# main.net
KiCad netlist of a schematic drawn in Altium Designer
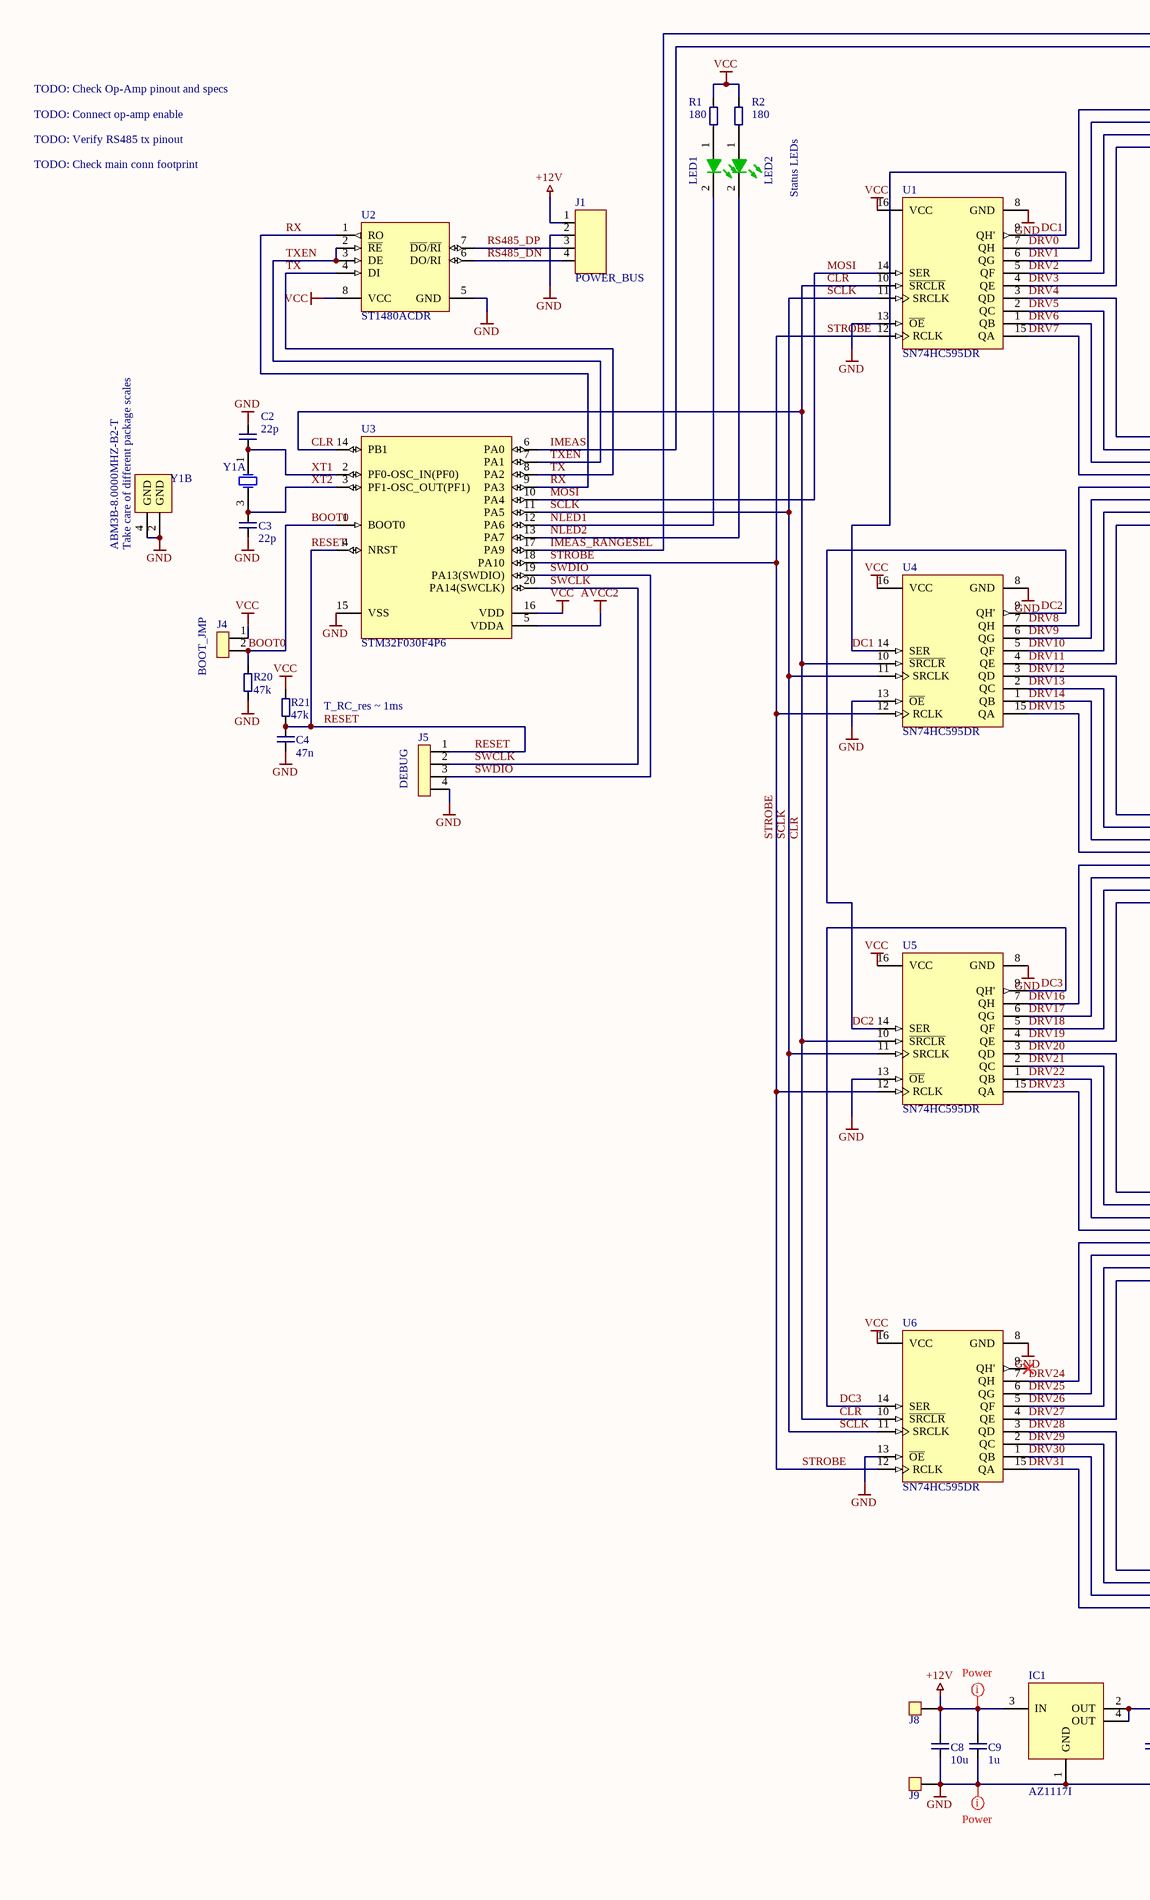
[diagram p0: main.SchDoc, left]
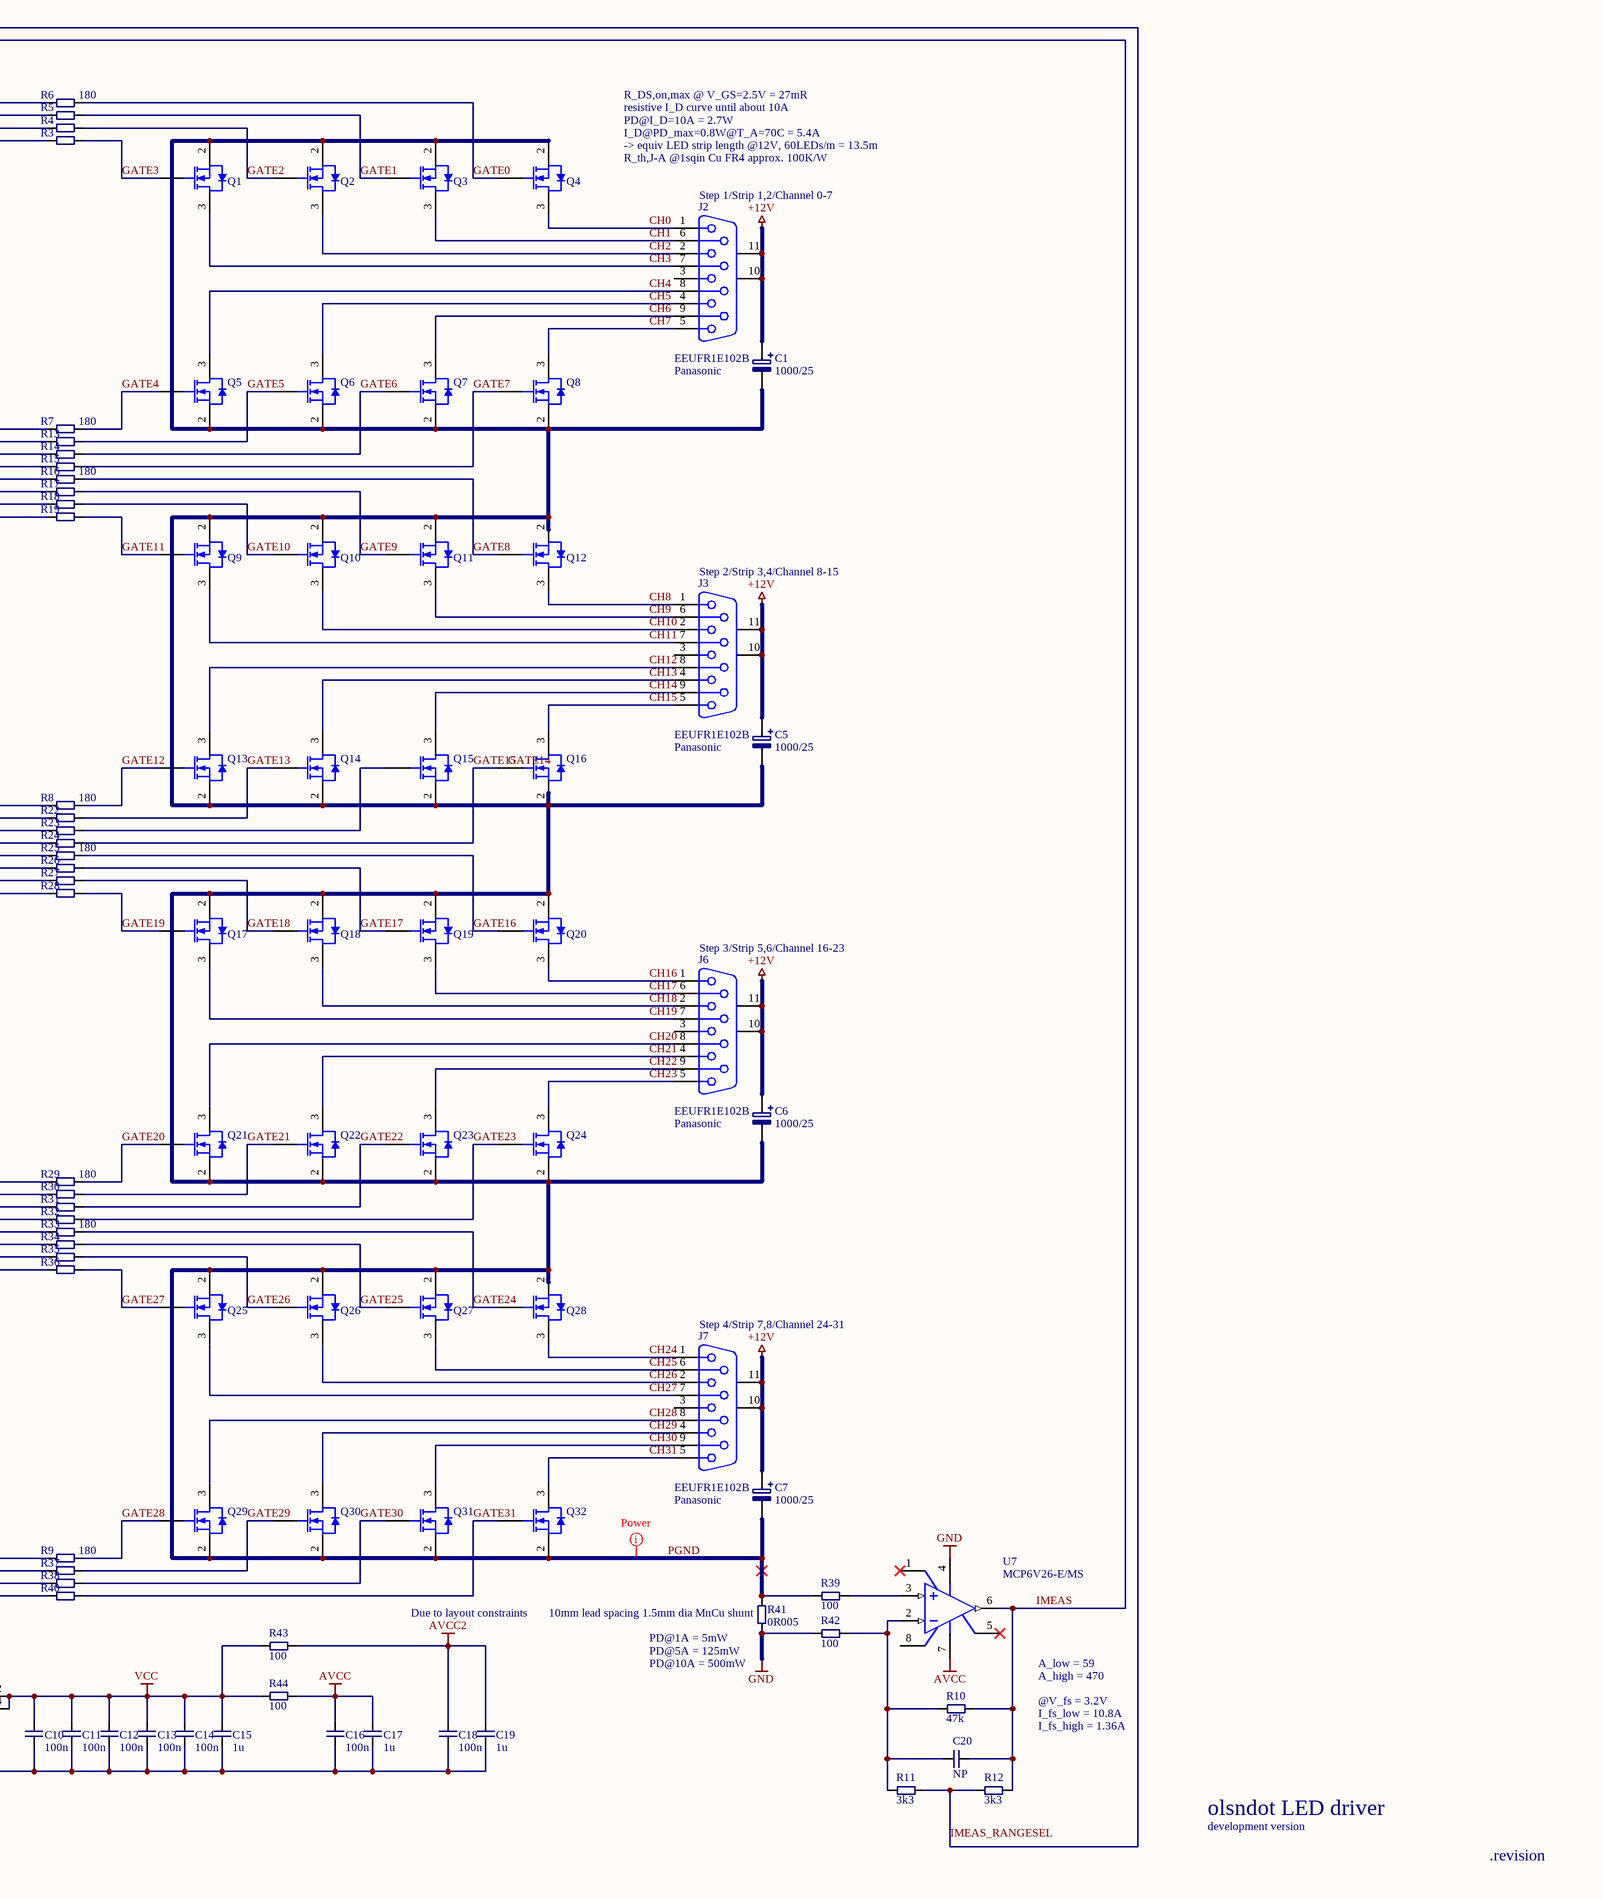
[diagram p1: main.SchDoc, right]

(export (version "E")
  (design (tool "Eeschema 10.0.6"))
  (components
    (comp (ref "C1")
      (value "1000/25")
      (footprint "ELKO_10mm_RM5")
      (fields (field (name "MFG PART NO") "EEUFR1E102B") (field (name "MFG") "Panasonic"))
      (libsource (lib "components") (part "ELKO"))
    )
    (comp (ref "C2")
      (value "22p")
      (footprint "J1-0603")
      (description "Capacitor")
      (libsource (lib "components") (part "C"))
    )
    (comp (ref "C3")
      (value "22p")
      (footprint "J1-0603")
      (description "Capacitor")
      (libsource (lib "components") (part "C"))
    )
    (comp (ref "C4")
      (value "47n")
      (footprint "J1-0603")
      (description "Capacitor")
      (libsource (lib "components") (part "C"))
    )
    (comp (ref "C5")
      (value "1000/25")
      (footprint "ELKO_10mm_RM5")
      (fields (field (name "MFG PART NO") "EEUFR1E102B") (field (name "MFG") "Panasonic"))
      (libsource (lib "components") (part "ELKO"))
    )
    (comp (ref "C6")
      (value "1000/25")
      (footprint "ELKO_10mm_RM5")
      (fields (field (name "MFG PART NO") "EEUFR1E102B") (field (name "MFG") "Panasonic"))
      (libsource (lib "components") (part "ELKO"))
    )
    (comp (ref "C7")
      (value "1000/25")
      (footprint "ELKO_10mm_RM5")
      (fields (field (name "MFG PART NO") "EEUFR1E102B") (field (name "MFG") "Panasonic"))
      (libsource (lib "components") (part "ELKO"))
    )
    (comp (ref "C8")
      (value "10u")
      (footprint "6-0805_M")
      (description "Capacitor")
      (libsource (lib "components") (part "C"))
    )
    (comp (ref "C9")
      (value "1u")
      (footprint "6-0805_M")
      (description "Capacitor")
      (libsource (lib "components") (part "C"))
    )
    (comp (ref "C10")
      (value "100n")
      (footprint "J1-0603")
      (description "Capacitor")
      (libsource (lib "components") (part "C"))
    )
    (comp (ref "C11")
      (value "100n")
      (footprint "J1-0603")
      (description "Capacitor")
      (libsource (lib "components") (part "C"))
    )
    (comp (ref "C12")
      (value "100n")
      (footprint "J1-0603")
      (description "Capacitor")
      (libsource (lib "components") (part "C"))
    )
    (comp (ref "C13")
      (value "100n")
      (footprint "J1-0603")
      (description "Capacitor")
      (libsource (lib "components") (part "C"))
    )
    (comp (ref "C14")
      (value "100n")
      (footprint "J1-0603")
      (description "Capacitor")
      (libsource (lib "components") (part "C"))
    )
    (comp (ref "C15")
      (value "1u")
      (footprint "6-0805_M")
      (description "Capacitor")
      (libsource (lib "components") (part "C"))
    )
    (comp (ref "C16")
      (value "100n")
      (footprint "J1-0603")
      (description "Capacitor")
      (libsource (lib "components") (part "C"))
    )
    (comp (ref "C17")
      (value "1u")
      (footprint "6-0805_M")
      (description "Capacitor")
      (libsource (lib "components") (part "C"))
    )
    (comp (ref "C18")
      (value "100n")
      (footprint "J1-0603")
      (description "Capacitor")
      (libsource (lib "components") (part "C"))
    )
    (comp (ref "C19")
      (value "1u")
      (footprint "J1-0603")
      (description "Capacitor")
      (libsource (lib "components") (part "C"))
    )
    (comp (ref "C20")
      (value "NP")
      (footprint "J1-0603")
      (description "Capacitor")
      (libsource (lib "components") (part "C"))
    )
    (comp (ref "IC1")
      (value "AZ1117I")
      (footprint "SOT223_M")
      (description "LDO, industrial temp range")
      (libsource (lib "components") (part "AZ1117I"))
    )
    (comp (ref "J1")
      (value "POWER_BUS")
      (footprint "TB_5.08_4P_FLANGE")
      (libsource (lib "components") (part "Phoenix_PT1,5/4-5,0H"))
    )
    (comp (ref "J2")
      (value "Step 1/Strip 1,2/Channel 0-7")
      (footprint "DSUB1.385-2H9")
      (description "Receptacle Assembly, 9 Position, Right Angle")
      (fields (field (name "PUBLISHER") "Altium Limited"))
      (libsource (lib "Miscellaneous Connectors") (part "D Connector 9"))
    )
    (comp (ref "J3")
      (value "Step 2/Strip 3,4/Channel 8-15")
      (footprint "DSUB1.385-2H9")
      (description "Receptacle Assembly, 9 Position, Right Angle")
      (fields (field (name "PUBLISHER") "Altium Limited"))
      (libsource (lib "Miscellaneous Connectors") (part "D Connector 9"))
    )
    (comp (ref "J4")
      (value "BOOT_JMP")
      (footprint "JUMPER_2P")
      (description "Jumper")
      (libsource (lib "components") (part "JUMPER"))
    )
    (comp (ref "J5")
      (value "DEBUG")
      (footprint "PINHD_4x1_100mil")
      (description "Pin Header 4x1 pin")
      (libsource (lib "components") (part "PH_4x1"))
    )
    (comp (ref "J6")
      (value "Step 3/Strip 5,6/Channel 16-23")
      (footprint "DSUB1.385-2H9")
      (description "Receptacle Assembly, 9 Position, Right Angle")
      (fields (field (name "PUBLISHER") "Altium Limited"))
      (libsource (lib "Miscellaneous Connectors") (part "D Connector 9"))
    )
    (comp (ref "J7")
      (value "Step 4/Strip 7,8/Channel 24-31")
      (footprint "DSUB1.385-2H9")
      (description "Receptacle Assembly, 9 Position, Right Angle")
      (fields (field (name "PUBLISHER") "Altium Limited"))
      (libsource (lib "Miscellaneous Connectors") (part "D Connector 9"))
    )
    (comp (ref "J8") (value "+12V") (libsource (lib "components") (part "TESTPOINT")))
    (comp (ref "J9") (value "GND") (libsource (lib "components") (part "TESTPOINT")))
    (comp (ref "LED1")
      (value "KP-1608MGC")
      (footprint "KING-0603LED_GREEN_V")
      (description "LED, SMT, 0603(1608), 1.1mm thickness, Green")
      (fields (field (name "MANUFACTURER") "Kingbright"))
      (libsource (lib "components") (part "CMP-0404-00001-1"))
    )
    (comp (ref "LED2")
      (value "KP-1608MGC")
      (footprint "KING-0603LED_GREEN_V")
      (description "LED, SMT, 0603(1608), 1.1mm thickness, Green")
      (fields (field (name "MANUFACTURER") "Kingbright"))
      (libsource (lib "components") (part "CMP-0404-00001-1"))
    )
    (comp (ref "Q1")
      (value "IRLML6244TRPbF")
      (footprint "ONSC-SOT-23-3-318-08_V")
      (description "Power MOSFET, 500 mA, 60 V, N-Channel, 3-Pin SOT-23, Pb-Free, Tape and Reel")
      (fields (field (name "MANUFACTURER") "On Semiconductor") (field (name "PARTNUMBER") "NVBF170LT1G"))
      (libsource (lib "Altium Content Vault") (part "ONSC-NMOS-G1S2D3-3"))
    )
    (comp (ref "Q2")
      (value "IRLML6244TRPbF")
      (footprint "ONSC-SOT-23-3-318-08_V")
      (description "Power MOSFET, 500 mA, 60 V, N-Channel, 3-Pin SOT-23, Pb-Free, Tape and Reel")
      (fields (field (name "MANUFACTURER") "On Semiconductor") (field (name "PARTNUMBER") "NVBF170LT1G"))
      (libsource (lib "Altium Content Vault") (part "ONSC-NMOS-G1S2D3-3"))
    )
    (comp (ref "Q3")
      (value "IRLML6244TRPbF")
      (footprint "ONSC-SOT-23-3-318-08_V")
      (description "Power MOSFET, 500 mA, 60 V, N-Channel, 3-Pin SOT-23, Pb-Free, Tape and Reel")
      (fields (field (name "MANUFACTURER") "On Semiconductor") (field (name "PARTNUMBER") "NVBF170LT1G"))
      (libsource (lib "Altium Content Vault") (part "ONSC-NMOS-G1S2D3-3"))
    )
    (comp (ref "Q4")
      (value "IRLML6244TRPbF")
      (footprint "ONSC-SOT-23-3-318-08_V")
      (description "Power MOSFET, 500 mA, 60 V, N-Channel, 3-Pin SOT-23, Pb-Free, Tape and Reel")
      (fields (field (name "MANUFACTURER") "On Semiconductor") (field (name "PARTNUMBER") "NVBF170LT1G"))
      (libsource (lib "Altium Content Vault") (part "ONSC-NMOS-G1S2D3-3"))
    )
    (comp (ref "Q5")
      (value "IRLML6244TRPbF")
      (footprint "ONSC-SOT-23-3-318-08_V")
      (description "Power MOSFET, 500 mA, 60 V, N-Channel, 3-Pin SOT-23, Pb-Free, Tape and Reel")
      (fields (field (name "MANUFACTURER") "On Semiconductor") (field (name "PARTNUMBER") "NVBF170LT1G"))
      (libsource (lib "Altium Content Vault") (part "ONSC-NMOS-G1S2D3-3"))
    )
    (comp (ref "Q6")
      (value "IRLML6244TRPbF")
      (footprint "ONSC-SOT-23-3-318-08_V")
      (description "Power MOSFET, 500 mA, 60 V, N-Channel, 3-Pin SOT-23, Pb-Free, Tape and Reel")
      (fields (field (name "MANUFACTURER") "On Semiconductor") (field (name "PARTNUMBER") "NVBF170LT1G"))
      (libsource (lib "Altium Content Vault") (part "ONSC-NMOS-G1S2D3-3"))
    )
    (comp (ref "Q7")
      (value "IRLML6244TRPbF")
      (footprint "ONSC-SOT-23-3-318-08_V")
      (description "Power MOSFET, 500 mA, 60 V, N-Channel, 3-Pin SOT-23, Pb-Free, Tape and Reel")
      (fields (field (name "MANUFACTURER") "On Semiconductor") (field (name "PARTNUMBER") "NVBF170LT1G"))
      (libsource (lib "Altium Content Vault") (part "ONSC-NMOS-G1S2D3-3"))
    )
    (comp (ref "Q8")
      (value "IRLML6244TRPbF")
      (footprint "ONSC-SOT-23-3-318-08_V")
      (description "Power MOSFET, 500 mA, 60 V, N-Channel, 3-Pin SOT-23, Pb-Free, Tape and Reel")
      (fields (field (name "MANUFACTURER") "On Semiconductor") (field (name "PARTNUMBER") "NVBF170LT1G"))
      (libsource (lib "Altium Content Vault") (part "ONSC-NMOS-G1S2D3-3"))
    )
    (comp (ref "Q9")
      (value "IRLML6244TRPbF")
      (footprint "ONSC-SOT-23-3-318-08_V")
      (description "Power MOSFET, 500 mA, 60 V, N-Channel, 3-Pin SOT-23, Pb-Free, Tape and Reel")
      (fields (field (name "MANUFACTURER") "On Semiconductor") (field (name "PARTNUMBER") "NVBF170LT1G"))
      (libsource (lib "Altium Content Vault") (part "ONSC-NMOS-G1S2D3-3"))
    )
    (comp (ref "Q10")
      (value "IRLML6244TRPbF")
      (footprint "ONSC-SOT-23-3-318-08_V")
      (description "Power MOSFET, 500 mA, 60 V, N-Channel, 3-Pin SOT-23, Pb-Free, Tape and Reel")
      (fields (field (name "MANUFACTURER") "On Semiconductor") (field (name "PARTNUMBER") "NVBF170LT1G"))
      (libsource (lib "Altium Content Vault") (part "ONSC-NMOS-G1S2D3-3"))
    )
    (comp (ref "Q11")
      (value "IRLML6244TRPbF")
      (footprint "ONSC-SOT-23-3-318-08_V")
      (description "Power MOSFET, 500 mA, 60 V, N-Channel, 3-Pin SOT-23, Pb-Free, Tape and Reel")
      (fields (field (name "MANUFACTURER") "On Semiconductor") (field (name "PARTNUMBER") "NVBF170LT1G"))
      (libsource (lib "Altium Content Vault") (part "ONSC-NMOS-G1S2D3-3"))
    )
    (comp (ref "Q12")
      (value "IRLML6244TRPbF")
      (footprint "ONSC-SOT-23-3-318-08_V")
      (description "Power MOSFET, 500 mA, 60 V, N-Channel, 3-Pin SOT-23, Pb-Free, Tape and Reel")
      (fields (field (name "MANUFACTURER") "On Semiconductor") (field (name "PARTNUMBER") "NVBF170LT1G"))
      (libsource (lib "Altium Content Vault") (part "ONSC-NMOS-G1S2D3-3"))
    )
    (comp (ref "Q13")
      (value "IRLML6244TRPbF")
      (footprint "ONSC-SOT-23-3-318-08_V")
      (description "Power MOSFET, 500 mA, 60 V, N-Channel, 3-Pin SOT-23, Pb-Free, Tape and Reel")
      (fields (field (name "MANUFACTURER") "On Semiconductor") (field (name "PARTNUMBER") "NVBF170LT1G"))
      (libsource (lib "Altium Content Vault") (part "ONSC-NMOS-G1S2D3-3"))
    )
    (comp (ref "Q14")
      (value "IRLML6244TRPbF")
      (footprint "ONSC-SOT-23-3-318-08_V")
      (description "Power MOSFET, 500 mA, 60 V, N-Channel, 3-Pin SOT-23, Pb-Free, Tape and Reel")
      (fields (field (name "MANUFACTURER") "On Semiconductor") (field (name "PARTNUMBER") "NVBF170LT1G"))
      (libsource (lib "Altium Content Vault") (part "ONSC-NMOS-G1S2D3-3"))
    )
    (comp (ref "Q15")
      (value "IRLML6244TRPbF")
      (footprint "ONSC-SOT-23-3-318-08_V")
      (description "Power MOSFET, 500 mA, 60 V, N-Channel, 3-Pin SOT-23, Pb-Free, Tape and Reel")
      (fields (field (name "MANUFACTURER") "On Semiconductor") (field (name "PARTNUMBER") "NVBF170LT1G"))
      (libsource (lib "Altium Content Vault") (part "ONSC-NMOS-G1S2D3-3"))
    )
    (comp (ref "Q16")
      (value "IRLML6244TRPbF")
      (footprint "ONSC-SOT-23-3-318-08_V")
      (description "Power MOSFET, 500 mA, 60 V, N-Channel, 3-Pin SOT-23, Pb-Free, Tape and Reel")
      (fields (field (name "MANUFACTURER") "On Semiconductor") (field (name "PARTNUMBER") "NVBF170LT1G"))
      (libsource (lib "Altium Content Vault") (part "ONSC-NMOS-G1S2D3-3"))
    )
    (comp (ref "Q17")
      (value "IRLML6244TRPbF")
      (footprint "ONSC-SOT-23-3-318-08_V")
      (description "Power MOSFET, 500 mA, 60 V, N-Channel, 3-Pin SOT-23, Pb-Free, Tape and Reel")
      (fields (field (name "MANUFACTURER") "On Semiconductor") (field (name "PARTNUMBER") "NVBF170LT1G"))
      (libsource (lib "Altium Content Vault") (part "ONSC-NMOS-G1S2D3-3"))
    )
    (comp (ref "Q18")
      (value "IRLML6244TRPbF")
      (footprint "ONSC-SOT-23-3-318-08_V")
      (description "Power MOSFET, 500 mA, 60 V, N-Channel, 3-Pin SOT-23, Pb-Free, Tape and Reel")
      (fields (field (name "MANUFACTURER") "On Semiconductor") (field (name "PARTNUMBER") "NVBF170LT1G"))
      (libsource (lib "Altium Content Vault") (part "ONSC-NMOS-G1S2D3-3"))
    )
    (comp (ref "Q19")
      (value "IRLML6244TRPbF")
      (footprint "ONSC-SOT-23-3-318-08_V")
      (description "Power MOSFET, 500 mA, 60 V, N-Channel, 3-Pin SOT-23, Pb-Free, Tape and Reel")
      (fields (field (name "MANUFACTURER") "On Semiconductor") (field (name "PARTNUMBER") "NVBF170LT1G"))
      (libsource (lib "Altium Content Vault") (part "ONSC-NMOS-G1S2D3-3"))
    )
    (comp (ref "Q20")
      (value "IRLML6244TRPbF")
      (footprint "ONSC-SOT-23-3-318-08_V")
      (description "Power MOSFET, 500 mA, 60 V, N-Channel, 3-Pin SOT-23, Pb-Free, Tape and Reel")
      (fields (field (name "MANUFACTURER") "On Semiconductor") (field (name "PARTNUMBER") "NVBF170LT1G"))
      (libsource (lib "Altium Content Vault") (part "ONSC-NMOS-G1S2D3-3"))
    )
    (comp (ref "Q21")
      (value "IRLML6244TRPbF")
      (footprint "ONSC-SOT-23-3-318-08_V")
      (description "Power MOSFET, 500 mA, 60 V, N-Channel, 3-Pin SOT-23, Pb-Free, Tape and Reel")
      (fields (field (name "MANUFACTURER") "On Semiconductor") (field (name "PARTNUMBER") "NVBF170LT1G"))
      (libsource (lib "Altium Content Vault") (part "ONSC-NMOS-G1S2D3-3"))
    )
    (comp (ref "Q22")
      (value "IRLML6244TRPbF")
      (footprint "ONSC-SOT-23-3-318-08_V")
      (description "Power MOSFET, 500 mA, 60 V, N-Channel, 3-Pin SOT-23, Pb-Free, Tape and Reel")
      (fields (field (name "MANUFACTURER") "On Semiconductor") (field (name "PARTNUMBER") "NVBF170LT1G"))
      (libsource (lib "Altium Content Vault") (part "ONSC-NMOS-G1S2D3-3"))
    )
    (comp (ref "Q23")
      (value "IRLML6244TRPbF")
      (footprint "ONSC-SOT-23-3-318-08_V")
      (description "Power MOSFET, 500 mA, 60 V, N-Channel, 3-Pin SOT-23, Pb-Free, Tape and Reel")
      (fields (field (name "MANUFACTURER") "On Semiconductor") (field (name "PARTNUMBER") "NVBF170LT1G"))
      (libsource (lib "Altium Content Vault") (part "ONSC-NMOS-G1S2D3-3"))
    )
    (comp (ref "Q24")
      (value "IRLML6244TRPbF")
      (footprint "ONSC-SOT-23-3-318-08_V")
      (description "Power MOSFET, 500 mA, 60 V, N-Channel, 3-Pin SOT-23, Pb-Free, Tape and Reel")
      (fields (field (name "MANUFACTURER") "On Semiconductor") (field (name "PARTNUMBER") "NVBF170LT1G"))
      (libsource (lib "Altium Content Vault") (part "ONSC-NMOS-G1S2D3-3"))
    )
    (comp (ref "Q25")
      (value "IRLML6244TRPbF")
      (footprint "ONSC-SOT-23-3-318-08_V")
      (description "Power MOSFET, 500 mA, 60 V, N-Channel, 3-Pin SOT-23, Pb-Free, Tape and Reel")
      (fields (field (name "MANUFACTURER") "On Semiconductor") (field (name "PARTNUMBER") "NVBF170LT1G"))
      (libsource (lib "Altium Content Vault") (part "ONSC-NMOS-G1S2D3-3"))
    )
    (comp (ref "Q26")
      (value "IRLML6244TRPbF")
      (footprint "ONSC-SOT-23-3-318-08_V")
      (description "Power MOSFET, 500 mA, 60 V, N-Channel, 3-Pin SOT-23, Pb-Free, Tape and Reel")
      (fields (field (name "MANUFACTURER") "On Semiconductor") (field (name "PARTNUMBER") "NVBF170LT1G"))
      (libsource (lib "Altium Content Vault") (part "ONSC-NMOS-G1S2D3-3"))
    )
    (comp (ref "Q27")
      (value "IRLML6244TRPbF")
      (footprint "ONSC-SOT-23-3-318-08_V")
      (description "Power MOSFET, 500 mA, 60 V, N-Channel, 3-Pin SOT-23, Pb-Free, Tape and Reel")
      (fields (field (name "MANUFACTURER") "On Semiconductor") (field (name "PARTNUMBER") "NVBF170LT1G"))
      (libsource (lib "Altium Content Vault") (part "ONSC-NMOS-G1S2D3-3"))
    )
    (comp (ref "Q28")
      (value "IRLML6244TRPbF")
      (footprint "ONSC-SOT-23-3-318-08_V")
      (description "Power MOSFET, 500 mA, 60 V, N-Channel, 3-Pin SOT-23, Pb-Free, Tape and Reel")
      (fields (field (name "MANUFACTURER") "On Semiconductor") (field (name "PARTNUMBER") "NVBF170LT1G"))
      (libsource (lib "Altium Content Vault") (part "ONSC-NMOS-G1S2D3-3"))
    )
    (comp (ref "Q29")
      (value "IRLML6244TRPbF")
      (footprint "ONSC-SOT-23-3-318-08_V")
      (description "Power MOSFET, 500 mA, 60 V, N-Channel, 3-Pin SOT-23, Pb-Free, Tape and Reel")
      (fields (field (name "MANUFACTURER") "On Semiconductor") (field (name "PARTNUMBER") "NVBF170LT1G"))
      (libsource (lib "Altium Content Vault") (part "ONSC-NMOS-G1S2D3-3"))
    )
    (comp (ref "Q30")
      (value "IRLML6244TRPbF")
      (footprint "ONSC-SOT-23-3-318-08_V")
      (description "Power MOSFET, 500 mA, 60 V, N-Channel, 3-Pin SOT-23, Pb-Free, Tape and Reel")
      (fields (field (name "MANUFACTURER") "On Semiconductor") (field (name "PARTNUMBER") "NVBF170LT1G"))
      (libsource (lib "Altium Content Vault") (part "ONSC-NMOS-G1S2D3-3"))
    )
    (comp (ref "Q31")
      (value "IRLML6244TRPbF")
      (footprint "ONSC-SOT-23-3-318-08_V")
      (description "Power MOSFET, 500 mA, 60 V, N-Channel, 3-Pin SOT-23, Pb-Free, Tape and Reel")
      (fields (field (name "MANUFACTURER") "On Semiconductor") (field (name "PARTNUMBER") "NVBF170LT1G"))
      (libsource (lib "Altium Content Vault") (part "ONSC-NMOS-G1S2D3-3"))
    )
    (comp (ref "Q32")
      (value "IRLML6244TRPbF")
      (footprint "ONSC-SOT-23-3-318-08_V")
      (description "Power MOSFET, 500 mA, 60 V, N-Channel, 3-Pin SOT-23, Pb-Free, Tape and Reel")
      (fields (field (name "MANUFACTURER") "On Semiconductor") (field (name "PARTNUMBER") "NVBF170LT1G"))
      (libsource (lib "Altium Content Vault") (part "ONSC-NMOS-G1S2D3-3"))
    )
    (comp (ref "R1")
      (value "180")
      (footprint "J1-0603")
      (description "Resistor")
      (libsource (lib "components") (part "R"))
    )
    (comp (ref "R2")
      (value "180")
      (footprint "J1-0603")
      (description "Resistor")
      (libsource (lib "components") (part "R"))
    )
    (comp (ref "R3")
      (value "180")
      (footprint "J1-0603")
      (description "Resistor")
      (libsource (lib "components") (part "R"))
    )
    (comp (ref "R4")
      (value "180")
      (footprint "J1-0603")
      (description "Resistor")
      (libsource (lib "components") (part "R"))
    )
    (comp (ref "R5")
      (value "180")
      (footprint "J1-0603")
      (description "Resistor")
      (libsource (lib "components") (part "R"))
    )
    (comp (ref "R6")
      (value "180")
      (footprint "J1-0603")
      (description "Resistor")
      (libsource (lib "components") (part "R"))
    )
    (comp (ref "R7")
      (value "180")
      (footprint "J1-0603")
      (description "Resistor")
      (libsource (lib "components") (part "R"))
    )
    (comp (ref "R8")
      (value "180")
      (footprint "J1-0603")
      (description "Resistor")
      (libsource (lib "components") (part "R"))
    )
    (comp (ref "R9")
      (value "180")
      (footprint "J1-0603")
      (description "Resistor")
      (libsource (lib "components") (part "R"))
    )
    (comp (ref "R10")
      (value "47k")
      (footprint "J1-0603")
      (description "Resistor")
      (libsource (lib "components") (part "R"))
    )
    (comp (ref "R11")
      (value "3k3")
      (footprint "J1-0603")
      (description "Resistor")
      (libsource (lib "components") (part "R"))
    )
    (comp (ref "R12")
      (value "3k3")
      (footprint "J1-0603")
      (description "Resistor")
      (libsource (lib "components") (part "R"))
    )
    (comp (ref "R13")
      (value "180")
      (footprint "J1-0603")
      (description "Resistor")
      (libsource (lib "components") (part "R"))
    )
    (comp (ref "R14")
      (value "180")
      (footprint "J1-0603")
      (description "Resistor")
      (libsource (lib "components") (part "R"))
    )
    (comp (ref "R15")
      (value "180")
      (footprint "J1-0603")
      (description "Resistor")
      (libsource (lib "components") (part "R"))
    )
    (comp (ref "R16")
      (value "180")
      (footprint "J1-0603")
      (description "Resistor")
      (libsource (lib "components") (part "R"))
    )
    (comp (ref "R17")
      (value "180")
      (footprint "J1-0603")
      (description "Resistor")
      (libsource (lib "components") (part "R"))
    )
    (comp (ref "R18")
      (value "180")
      (footprint "J1-0603")
      (description "Resistor")
      (libsource (lib "components") (part "R"))
    )
    (comp (ref "R19")
      (value "180")
      (footprint "J1-0603")
      (description "Resistor")
      (libsource (lib "components") (part "R"))
    )
    (comp (ref "R20")
      (value "47k")
      (footprint "J1-0603")
      (description "Resistor")
      (libsource (lib "components") (part "R"))
    )
    (comp (ref "R21")
      (value "47k")
      (footprint "J1-0603")
      (description "Resistor")
      (libsource (lib "components") (part "R"))
    )
    (comp (ref "R22")
      (value "180")
      (footprint "J1-0603")
      (description "Resistor")
      (libsource (lib "components") (part "R"))
    )
    (comp (ref "R23")
      (value "180")
      (footprint "J1-0603")
      (description "Resistor")
      (libsource (lib "components") (part "R"))
    )
    (comp (ref "R24")
      (value "180")
      (footprint "J1-0603")
      (description "Resistor")
      (libsource (lib "components") (part "R"))
    )
    (comp (ref "R25")
      (value "180")
      (footprint "J1-0603")
      (description "Resistor")
      (libsource (lib "components") (part "R"))
    )
    (comp (ref "R26")
      (value "180")
      (footprint "J1-0603")
      (description "Resistor")
      (libsource (lib "components") (part "R"))
    )
    (comp (ref "R27")
      (value "180")
      (footprint "J1-0603")
      (description "Resistor")
      (libsource (lib "components") (part "R"))
    )
    (comp (ref "R28")
      (value "180")
      (footprint "J1-0603")
      (description "Resistor")
      (libsource (lib "components") (part "R"))
    )
    (comp (ref "R29")
      (value "180")
      (footprint "J1-0603")
      (description "Resistor")
      (libsource (lib "components") (part "R"))
    )
    (comp (ref "R30")
      (value "180")
      (footprint "J1-0603")
      (description "Resistor")
      (libsource (lib "components") (part "R"))
    )
    (comp (ref "R31")
      (value "180")
      (footprint "J1-0603")
      (description "Resistor")
      (libsource (lib "components") (part "R"))
    )
    (comp (ref "R32")
      (value "180")
      (footprint "J1-0603")
      (description "Resistor")
      (libsource (lib "components") (part "R"))
    )
    (comp (ref "R33")
      (value "180")
      (footprint "J1-0603")
      (description "Resistor")
      (libsource (lib "components") (part "R"))
    )
    (comp (ref "R34")
      (value "180")
      (footprint "J1-0603")
      (description "Resistor")
      (libsource (lib "components") (part "R"))
    )
    (comp (ref "R35")
      (value "180")
      (footprint "J1-0603")
      (description "Resistor")
      (libsource (lib "components") (part "R"))
    )
    (comp (ref "R36")
      (value "180")
      (footprint "J1-0603")
      (description "Resistor")
      (libsource (lib "components") (part "R"))
    )
    (comp (ref "R37")
      (value "180")
      (footprint "J1-0603")
      (description "Resistor")
      (libsource (lib "components") (part "R"))
    )
    (comp (ref "R38")
      (value "180")
      (footprint "J1-0603")
      (description "Resistor")
      (libsource (lib "components") (part "R"))
    )
    (comp (ref "R39")
      (value "100")
      (footprint "J1-0603")
      (description "Resistor")
      (libsource (lib "components") (part "R"))
    )
    (comp (ref "R40")
      (value "180")
      (footprint "J1-0603")
      (description "Resistor")
      (libsource (lib "components") (part "R"))
    )
    (comp (ref "R41")
      (value "0R005")
      (footprint "10x1.5mm_Shunt")
      (description "Resistor")
      (fields (field (name "MECHANICAL") "10mm lead spacing 1.5mm dia MnCu shunt"))
      (libsource (lib "components") (part "R"))
    )
    (comp (ref "R42")
      (value "100")
      (footprint "J1-0603")
      (description "Resistor")
      (libsource (lib "components") (part "R"))
    )
    (comp (ref "R43")
      (value "100")
      (footprint "J1-0603")
      (description "Resistor")
      (libsource (lib "components") (part "R"))
    )
    (comp (ref "R44")
      (value "100")
      (footprint "J1-0603")
      (description "Resistor")
      (libsource (lib "components") (part "R"))
    )
    (comp (ref "U1")
      (value "SN74HC595DR")
      (footprint "D0016A_M")
      (description "8-Bit Shift Registers With 3-State Output Registers, D0016A, LARGE T&R")
      (fields
        (field (name "GENERIC PART NUMBER") "SN74HC595")
        (field (name "MANUFACTURER") "Texas Instruments")
      )
      (libsource (lib "Altium Content Vault") (part "CMP-0780-00037-3"))
    )
    (comp (ref "U2")
      (value "ST1480ACDR")
      (footprint "SO8_M")
      (description "Multipoint RS-485/RS-422 Transceiver, 8-pin Narrow SOIC")
      (fields (field (name "MANUFACTURER") "National Semiconductor"))
      (libsource (lib "components") (part "IN-LNTX-DS75176B"))
    )
    (comp (ref "U3")
      (value "STM32F030F4P6")
      (footprint "STM-TSSOP20_L")
      (libsource (lib "Altium Content Vault") (part "MC-ARM-STM32F030-IL20"))
    )
    (comp (ref "U4")
      (value "SN74HC595DR")
      (footprint "D0016A_M")
      (description "8-Bit Shift Registers With 3-State Output Registers, D0016A, LARGE T&R")
      (fields
        (field (name "GENERIC PART NUMBER") "SN74HC595")
        (field (name "MANUFACTURER") "Texas Instruments")
      )
      (libsource (lib "Altium Content Vault") (part "CMP-0780-00037-3"))
    )
    (comp (ref "U5")
      (value "SN74HC595DR")
      (footprint "D0016A_M")
      (description "8-Bit Shift Registers With 3-State Output Registers, D0016A, LARGE T&R")
      (fields
        (field (name "GENERIC PART NUMBER") "SN74HC595")
        (field (name "MANUFACTURER") "Texas Instruments")
      )
      (libsource (lib "Altium Content Vault") (part "CMP-0780-00037-3"))
    )
    (comp (ref "U6")
      (value "SN74HC595DR")
      (footprint "D0016A_M")
      (description "8-Bit Shift Registers With 3-State Output Registers, D0016A, LARGE T&R")
      (fields
        (field (name "GENERIC PART NUMBER") "SN74HC595")
        (field (name "MANUFACTURER") "Texas Instruments")
      )
      (libsource (lib "Altium Content Vault") (part "CMP-0780-00037-3"))
    )
    (comp (ref "U7")
      (value "MCP6V26-E/MS")
      (footprint "MSOP-MS8_N")
      (description "620 渭A, 2 MHz Auto-Zeroed Op Amp, 8-Pin MSOP, Extended Temperature")
      (libsource (lib "Altium Content Vault") (part "AMP-OPA-MCP6V26-IL8"))
    )
    (comp (ref "Y1")
      (value "ABM3B-8.0000MHZ-B2-T")
      (footprint "XTAL_MJ_5x3.2")
      (description "Crystal, SMD, 25.000000MHz Stab=50ppm 18.0pF")
      (fields
        (field (name "MANUFACTURER") "Abracon")
        (field (name "PARTNUMBER") "ABM3B-25.000MHZ-B2-T")
        (field (name "NOTE") "Take care of different package scales")
      )
      (libsource (lib "components") (part "ABRA-ABM3B-4"))
    )
  )
  (nets
    (net (code "1") (name "+12V") (class "Default")
      (node (ref "C1") (pin "1") (pinfunction "1_1") (pintype "passive"))
      (node (ref "C5") (pin "1") (pinfunction "1_1") (pintype "passive"))
      (node (ref "C6") (pin "1") (pinfunction "1_1") (pintype "passive"))
      (node (ref "C7") (pin "1") (pinfunction "1_1") (pintype "passive"))
      (node (ref "C8") (pin "1") (pinfunction "1_1") (pintype "passive"))
      (node (ref "C9") (pin "1") (pinfunction "1_1") (pintype "passive"))
      (node (ref "IC1") (pin "3") (pinfunction "IN_3") (pintype "passive"))
      (node (ref "J1") (pin "1") (pintype "passive"))
      (node (ref "J2") (pin "10") (pinfunction "MH1_10") (pintype "passive"))
      (node (ref "J2") (pin "11") (pinfunction "MH2_11") (pintype "passive"))
      (node (ref "J3") (pin "10") (pinfunction "MH1_10") (pintype "passive"))
      (node (ref "J3") (pin "11") (pinfunction "MH2_11") (pintype "passive"))
      (node (ref "J6") (pin "10") (pinfunction "MH1_10") (pintype "passive"))
      (node (ref "J6") (pin "11") (pinfunction "MH2_11") (pintype "passive"))
      (node (ref "J7") (pin "10") (pinfunction "MH1_10") (pintype "passive"))
      (node (ref "J7") (pin "11") (pinfunction "MH2_11") (pintype "passive"))
      (node (ref "J8") (pin "1") (pinfunction "1_1") (pintype "passive"))
    )
    (net (code "2") (name "/BOOT0") (class "Default")
      (node (ref "J4") (pin "2") (pinfunction "2_2") (pintype "passive"))
      (node (ref "R20") (pin "2") (pinfunction "2_2") (pintype "passive"))
      (node (ref "U3") (pin "1") (pinfunction "BOOT0_1") (pintype "input"))
    )
    (net (code "3") (name "/CH0") (class "Default")
      (node (ref "J2") (pin "1") (pinfunction "1_1") (pintype "passive"))
      (node (ref "Q4") (pin "3") (pinfunction "D_3") (pintype "passive"))
    )
    (net (code "4") (name "/CH1") (class "Default")
      (node (ref "J2") (pin "6") (pinfunction "6_6") (pintype "passive"))
      (node (ref "Q3") (pin "3") (pinfunction "D_3") (pintype "passive"))
    )
    (net (code "5") (name "/CH2") (class "Default")
      (node (ref "J2") (pin "2") (pinfunction "2_2") (pintype "passive"))
      (node (ref "Q2") (pin "3") (pinfunction "D_3") (pintype "passive"))
    )
    (net (code "6") (name "/CH3") (class "Default")
      (node (ref "J2") (pin "7") (pinfunction "7_7") (pintype "passive"))
      (node (ref "Q1") (pin "3") (pinfunction "D_3") (pintype "passive"))
    )
    (net (code "7") (name "/CH4") (class "Default")
      (node (ref "J2") (pin "8") (pinfunction "8_8") (pintype "passive"))
      (node (ref "Q5") (pin "3") (pinfunction "D_3") (pintype "passive"))
    )
    (net (code "8") (name "/CH5") (class "Default")
      (node (ref "J2") (pin "4") (pinfunction "4_4") (pintype "passive"))
      (node (ref "Q6") (pin "3") (pinfunction "D_3") (pintype "passive"))
    )
    (net (code "9") (name "/CH6") (class "Default")
      (node (ref "J2") (pin "9") (pinfunction "9_9") (pintype "passive"))
      (node (ref "Q7") (pin "3") (pinfunction "D_3") (pintype "passive"))
    )
    (net (code "10") (name "/CH7") (class "Default")
      (node (ref "J2") (pin "5") (pinfunction "5_5") (pintype "passive"))
      (node (ref "Q8") (pin "3") (pinfunction "D_3") (pintype "passive"))
    )
    (net (code "11") (name "/CH8") (class "Default")
      (node (ref "J3") (pin "1") (pinfunction "1_1") (pintype "passive"))
      (node (ref "Q12") (pin "3") (pinfunction "D_3") (pintype "passive"))
    )
    (net (code "12") (name "/CH9") (class "Default")
      (node (ref "J3") (pin "6") (pinfunction "6_6") (pintype "passive"))
      (node (ref "Q11") (pin "3") (pinfunction "D_3") (pintype "passive"))
    )
    (net (code "13") (name "/CH10") (class "Default")
      (node (ref "J3") (pin "2") (pinfunction "2_2") (pintype "passive"))
      (node (ref "Q10") (pin "3") (pinfunction "D_3") (pintype "passive"))
    )
    (net (code "14") (name "/CH11") (class "Default")
      (node (ref "J3") (pin "7") (pinfunction "7_7") (pintype "passive"))
      (node (ref "Q9") (pin "3") (pinfunction "D_3") (pintype "passive"))
    )
    (net (code "15") (name "/CH12") (class "Default")
      (node (ref "J3") (pin "8") (pinfunction "8_8") (pintype "passive"))
      (node (ref "Q13") (pin "3") (pinfunction "D_3") (pintype "passive"))
    )
    (net (code "16") (name "/CH13") (class "Default")
      (node (ref "J3") (pin "4") (pinfunction "4_4") (pintype "passive"))
      (node (ref "Q14") (pin "3") (pinfunction "D_3") (pintype "passive"))
    )
    (net (code "17") (name "/CH14") (class "Default")
      (node (ref "J3") (pin "9") (pinfunction "9_9") (pintype "passive"))
      (node (ref "Q15") (pin "3") (pinfunction "D_3") (pintype "passive"))
    )
    (net (code "18") (name "/CH15") (class "Default")
      (node (ref "J3") (pin "5") (pinfunction "5_5") (pintype "passive"))
      (node (ref "Q16") (pin "3") (pinfunction "D_3") (pintype "passive"))
    )
    (net (code "19") (name "/CH16") (class "Default")
      (node (ref "J6") (pin "1") (pinfunction "1_1") (pintype "passive"))
      (node (ref "Q20") (pin "3") (pinfunction "D_3") (pintype "passive"))
    )
    (net (code "20") (name "/CH17") (class "Default")
      (node (ref "J6") (pin "6") (pinfunction "6_6") (pintype "passive"))
      (node (ref "Q19") (pin "3") (pinfunction "D_3") (pintype "passive"))
    )
    (net (code "21") (name "/CH18") (class "Default")
      (node (ref "J6") (pin "2") (pinfunction "2_2") (pintype "passive"))
      (node (ref "Q18") (pin "3") (pinfunction "D_3") (pintype "passive"))
    )
    (net (code "22") (name "/CH19") (class "Default")
      (node (ref "J6") (pin "7") (pinfunction "7_7") (pintype "passive"))
      (node (ref "Q17") (pin "3") (pinfunction "D_3") (pintype "passive"))
    )
    (net (code "23") (name "/CH20") (class "Default")
      (node (ref "J6") (pin "8") (pinfunction "8_8") (pintype "passive"))
      (node (ref "Q21") (pin "3") (pinfunction "D_3") (pintype "passive"))
    )
    (net (code "24") (name "/CH21") (class "Default")
      (node (ref "J6") (pin "4") (pinfunction "4_4") (pintype "passive"))
      (node (ref "Q22") (pin "3") (pinfunction "D_3") (pintype "passive"))
    )
    (net (code "25") (name "/CH22") (class "Default")
      (node (ref "J6") (pin "9") (pinfunction "9_9") (pintype "passive"))
      (node (ref "Q23") (pin "3") (pinfunction "D_3") (pintype "passive"))
    )
    (net (code "26") (name "/CH23") (class "Default")
      (node (ref "J6") (pin "5") (pinfunction "5_5") (pintype "passive"))
      (node (ref "Q24") (pin "3") (pinfunction "D_3") (pintype "passive"))
    )
    (net (code "27") (name "/CH24") (class "Default")
      (node (ref "J7") (pin "1") (pinfunction "1_1") (pintype "passive"))
      (node (ref "Q28") (pin "3") (pinfunction "D_3") (pintype "passive"))
    )
    (net (code "28") (name "/CH25") (class "Default")
      (node (ref "J7") (pin "6") (pinfunction "6_6") (pintype "passive"))
      (node (ref "Q27") (pin "3") (pinfunction "D_3") (pintype "passive"))
    )
    (net (code "29") (name "/CH26") (class "Default")
      (node (ref "J7") (pin "2") (pinfunction "2_2") (pintype "passive"))
      (node (ref "Q26") (pin "3") (pinfunction "D_3") (pintype "passive"))
    )
    (net (code "30") (name "/CH27") (class "Default")
      (node (ref "J7") (pin "7") (pinfunction "7_7") (pintype "passive"))
      (node (ref "Q25") (pin "3") (pinfunction "D_3") (pintype "passive"))
    )
    (net (code "31") (name "/CH28") (class "Default")
      (node (ref "J7") (pin "8") (pinfunction "8_8") (pintype "passive"))
      (node (ref "Q29") (pin "3") (pinfunction "D_3") (pintype "passive"))
    )
    (net (code "32") (name "/CH29") (class "Default")
      (node (ref "J7") (pin "4") (pinfunction "4_4") (pintype "passive"))
      (node (ref "Q30") (pin "3") (pinfunction "D_3") (pintype "passive"))
    )
    (net (code "33") (name "/CH30") (class "Default")
      (node (ref "J7") (pin "9") (pinfunction "9_9") (pintype "passive"))
      (node (ref "Q31") (pin "3") (pinfunction "D_3") (pintype "passive"))
    )
    (net (code "34") (name "/CH31") (class "Default")
      (node (ref "J7") (pin "5") (pinfunction "5_5") (pintype "passive"))
      (node (ref "Q32") (pin "3") (pinfunction "D_3") (pintype "passive"))
    )
    (net (code "35") (name "/CLR") (class "Default")
      (node (ref "U1") (pin "10") (pinfunction "~{SRCLR}_10") (pintype "input"))
      (node (ref "U3") (pin "14") (pinfunction "PB1_14") (pintype "bidirectional"))
      (node (ref "U4") (pin "10") (pinfunction "~{SRCLR}_10") (pintype "input"))
      (node (ref "U5") (pin "10") (pinfunction "~{SRCLR}_10") (pintype "input"))
      (node (ref "U6") (pin "10") (pinfunction "~{SRCLR}_10") (pintype "input"))
    )
    (net (code "36") (name "/DC1") (class "Default")
      (node (ref "U1") (pin "9") (pinfunction "QH'_9") (pintype "output"))
      (node (ref "U4") (pin "14") (pinfunction "SER_14") (pintype "input"))
    )
    (net (code "37") (name "/DC2") (class "Default")
      (node (ref "U4") (pin "9") (pinfunction "QH'_9") (pintype "output"))
      (node (ref "U5") (pin "14") (pinfunction "SER_14") (pintype "input"))
    )
    (net (code "38") (name "/DC3") (class "Default")
      (node (ref "U5") (pin "9") (pinfunction "QH'_9") (pintype "output"))
      (node (ref "U6") (pin "14") (pinfunction "SER_14") (pintype "input"))
    )
    (net (code "39") (name "/DRV0") (class "Default")
      (node (ref "R6") (pin "2") (pinfunction "2_2") (pintype "passive"))
      (node (ref "U1") (pin "7") (pinfunction "QH_7") (pintype "tri_state"))
    )
    (net (code "40") (name "/DRV1") (class "Default")
      (node (ref "R5") (pin "2") (pinfunction "2_2") (pintype "passive"))
      (node (ref "U1") (pin "6") (pinfunction "QG_6") (pintype "tri_state"))
    )
    (net (code "41") (name "/DRV2") (class "Default")
      (node (ref "R4") (pin "2") (pinfunction "2_2") (pintype "passive"))
      (node (ref "U1") (pin "5") (pinfunction "QF_5") (pintype "tri_state"))
    )
    (net (code "42") (name "/DRV3") (class "Default")
      (node (ref "R3") (pin "2") (pinfunction "2_2") (pintype "passive"))
      (node (ref "U1") (pin "4") (pinfunction "QE_4") (pintype "tri_state"))
    )
    (net (code "43") (name "/DRV4") (class "Default")
      (node (ref "R7") (pin "2") (pinfunction "2_2") (pintype "passive"))
      (node (ref "U1") (pin "3") (pinfunction "QD_3") (pintype "tri_state"))
    )
    (net (code "44") (name "/DRV5") (class "Default")
      (node (ref "R13") (pin "2") (pinfunction "2_2") (pintype "passive"))
      (node (ref "U1") (pin "2") (pinfunction "QC_2") (pintype "tri_state"))
    )
    (net (code "45") (name "/DRV6") (class "Default")
      (node (ref "R14") (pin "2") (pinfunction "2_2") (pintype "passive"))
      (node (ref "U1") (pin "1") (pinfunction "QB_1") (pintype "tri_state"))
    )
    (net (code "46") (name "/DRV7") (class "Default")
      (node (ref "R15") (pin "2") (pinfunction "2_2") (pintype "passive"))
      (node (ref "U1") (pin "15") (pinfunction "QA_15") (pintype "tri_state"))
    )
    (net (code "47") (name "/DRV8") (class "Default")
      (node (ref "R16") (pin "2") (pinfunction "2_2") (pintype "passive"))
      (node (ref "U4") (pin "7") (pinfunction "QH_7") (pintype "tri_state"))
    )
    (net (code "48") (name "/DRV9") (class "Default")
      (node (ref "R17") (pin "2") (pinfunction "2_2") (pintype "passive"))
      (node (ref "U4") (pin "6") (pinfunction "QG_6") (pintype "tri_state"))
    )
    (net (code "49") (name "/DRV10") (class "Default")
      (node (ref "R18") (pin "2") (pinfunction "2_2") (pintype "passive"))
      (node (ref "U4") (pin "5") (pinfunction "QF_5") (pintype "tri_state"))
    )
    (net (code "50") (name "/DRV11") (class "Default")
      (node (ref "R19") (pin "2") (pinfunction "2_2") (pintype "passive"))
      (node (ref "U4") (pin "4") (pinfunction "QE_4") (pintype "tri_state"))
    )
    (net (code "51") (name "/DRV12") (class "Default")
      (node (ref "R8") (pin "2") (pinfunction "2_2") (pintype "passive"))
      (node (ref "U4") (pin "3") (pinfunction "QD_3") (pintype "tri_state"))
    )
    (net (code "52") (name "/DRV13") (class "Default")
      (node (ref "R22") (pin "2") (pinfunction "2_2") (pintype "passive"))
      (node (ref "U4") (pin "2") (pinfunction "QC_2") (pintype "tri_state"))
    )
    (net (code "53") (name "/DRV14") (class "Default")
      (node (ref "R23") (pin "2") (pinfunction "2_2") (pintype "passive"))
      (node (ref "U4") (pin "1") (pinfunction "QB_1") (pintype "tri_state"))
    )
    (net (code "54") (name "/DRV15") (class "Default")
      (node (ref "R24") (pin "2") (pinfunction "2_2") (pintype "passive"))
      (node (ref "U4") (pin "15") (pinfunction "QA_15") (pintype "tri_state"))
    )
    (net (code "55") (name "/DRV16") (class "Default")
      (node (ref "R25") (pin "2") (pinfunction "2_2") (pintype "passive"))
      (node (ref "U5") (pin "7") (pinfunction "QH_7") (pintype "tri_state"))
    )
    (net (code "56") (name "/DRV17") (class "Default")
      (node (ref "R26") (pin "2") (pinfunction "2_2") (pintype "passive"))
      (node (ref "U5") (pin "6") (pinfunction "QG_6") (pintype "tri_state"))
    )
    (net (code "57") (name "/DRV18") (class "Default")
      (node (ref "R27") (pin "2") (pinfunction "2_2") (pintype "passive"))
      (node (ref "U5") (pin "5") (pinfunction "QF_5") (pintype "tri_state"))
    )
    (net (code "58") (name "/DRV19") (class "Default")
      (node (ref "R28") (pin "2") (pinfunction "2_2") (pintype "passive"))
      (node (ref "U5") (pin "4") (pinfunction "QE_4") (pintype "tri_state"))
    )
    (net (code "59") (name "/DRV20") (class "Default")
      (node (ref "R29") (pin "2") (pinfunction "2_2") (pintype "passive"))
      (node (ref "U5") (pin "3") (pinfunction "QD_3") (pintype "tri_state"))
    )
    (net (code "60") (name "/DRV21") (class "Default")
      (node (ref "R30") (pin "2") (pinfunction "2_2") (pintype "passive"))
      (node (ref "U5") (pin "2") (pinfunction "QC_2") (pintype "tri_state"))
    )
    (net (code "61") (name "/DRV22") (class "Default")
      (node (ref "R31") (pin "2") (pinfunction "2_2") (pintype "passive"))
      (node (ref "U5") (pin "1") (pinfunction "QB_1") (pintype "tri_state"))
    )
    (net (code "62") (name "/DRV23") (class "Default")
      (node (ref "R32") (pin "2") (pinfunction "2_2") (pintype "passive"))
      (node (ref "U5") (pin "15") (pinfunction "QA_15") (pintype "tri_state"))
    )
    (net (code "63") (name "/DRV24") (class "Default")
      (node (ref "R33") (pin "2") (pinfunction "2_2") (pintype "passive"))
      (node (ref "U6") (pin "7") (pinfunction "QH_7") (pintype "tri_state"))
    )
    (net (code "64") (name "/DRV25") (class "Default")
      (node (ref "R34") (pin "2") (pinfunction "2_2") (pintype "passive"))
      (node (ref "U6") (pin "6") (pinfunction "QG_6") (pintype "tri_state"))
    )
    (net (code "65") (name "/DRV26") (class "Default")
      (node (ref "R35") (pin "2") (pinfunction "2_2") (pintype "passive"))
      (node (ref "U6") (pin "5") (pinfunction "QF_5") (pintype "tri_state"))
    )
    (net (code "66") (name "/DRV27") (class "Default")
      (node (ref "R36") (pin "2") (pinfunction "2_2") (pintype "passive"))
      (node (ref "U6") (pin "4") (pinfunction "QE_4") (pintype "tri_state"))
    )
    (net (code "67") (name "/DRV28") (class "Default")
      (node (ref "R9") (pin "2") (pinfunction "2_2") (pintype "passive"))
      (node (ref "U6") (pin "3") (pinfunction "QD_3") (pintype "tri_state"))
    )
    (net (code "68") (name "/DRV29") (class "Default")
      (node (ref "R37") (pin "2") (pinfunction "2_2") (pintype "passive"))
      (node (ref "U6") (pin "2") (pinfunction "QC_2") (pintype "tri_state"))
    )
    (net (code "69") (name "/DRV30") (class "Default")
      (node (ref "R38") (pin "2") (pinfunction "2_2") (pintype "passive"))
      (node (ref "U6") (pin "1") (pinfunction "QB_1") (pintype "tri_state"))
    )
    (net (code "70") (name "/DRV31") (class "Default")
      (node (ref "R40") (pin "2") (pinfunction "2_2") (pintype "passive"))
      (node (ref "U6") (pin "15") (pinfunction "QA_15") (pintype "tri_state"))
    )
    (net (code "71") (name "/GATE0") (class "Default")
      (node (ref "Q4") (pin "1") (pinfunction "G_1") (pintype "passive"))
      (node (ref "R6") (pin "1") (pinfunction "1_1") (pintype "passive"))
    )
    (net (code "72") (name "/GATE1") (class "Default")
      (node (ref "Q3") (pin "1") (pinfunction "G_1") (pintype "passive"))
      (node (ref "R5") (pin "1") (pinfunction "1_1") (pintype "passive"))
    )
    (net (code "73") (name "/GATE2") (class "Default")
      (node (ref "Q2") (pin "1") (pinfunction "G_1") (pintype "passive"))
      (node (ref "R4") (pin "1") (pinfunction "1_1") (pintype "passive"))
    )
    (net (code "74") (name "/GATE3") (class "Default")
      (node (ref "Q1") (pin "1") (pinfunction "G_1") (pintype "passive"))
      (node (ref "R3") (pin "1") (pinfunction "1_1") (pintype "passive"))
    )
    (net (code "75") (name "/GATE4") (class "Default")
      (node (ref "Q5") (pin "1") (pinfunction "G_1") (pintype "passive"))
      (node (ref "R7") (pin "1") (pinfunction "1_1") (pintype "passive"))
    )
    (net (code "76") (name "/GATE5") (class "Default")
      (node (ref "Q6") (pin "1") (pinfunction "G_1") (pintype "passive"))
      (node (ref "R13") (pin "1") (pinfunction "1_1") (pintype "passive"))
    )
    (net (code "77") (name "/GATE6") (class "Default")
      (node (ref "Q7") (pin "1") (pinfunction "G_1") (pintype "passive"))
      (node (ref "R14") (pin "1") (pinfunction "1_1") (pintype "passive"))
    )
    (net (code "78") (name "/GATE7") (class "Default")
      (node (ref "Q8") (pin "1") (pinfunction "G_1") (pintype "passive"))
      (node (ref "R15") (pin "1") (pinfunction "1_1") (pintype "passive"))
    )
    (net (code "79") (name "/GATE8") (class "Default")
      (node (ref "Q12") (pin "1") (pinfunction "G_1") (pintype "passive"))
      (node (ref "R16") (pin "1") (pinfunction "1_1") (pintype "passive"))
    )
    (net (code "80") (name "/GATE9") (class "Default")
      (node (ref "Q11") (pin "1") (pinfunction "G_1") (pintype "passive"))
      (node (ref "R17") (pin "1") (pinfunction "1_1") (pintype "passive"))
    )
    (net (code "81") (name "/GATE10") (class "Default")
      (node (ref "Q10") (pin "1") (pinfunction "G_1") (pintype "passive"))
      (node (ref "R18") (pin "1") (pinfunction "1_1") (pintype "passive"))
    )
    (net (code "82") (name "/GATE11") (class "Default")
      (node (ref "Q9") (pin "1") (pinfunction "G_1") (pintype "passive"))
      (node (ref "R19") (pin "1") (pinfunction "1_1") (pintype "passive"))
    )
    (net (code "83") (name "/GATE12") (class "Default")
      (node (ref "Q13") (pin "1") (pinfunction "G_1") (pintype "passive"))
      (node (ref "R8") (pin "1") (pinfunction "1_1") (pintype "passive"))
    )
    (net (code "84") (name "/GATE13") (class "Default")
      (node (ref "Q14") (pin "1") (pinfunction "G_1") (pintype "passive"))
      (node (ref "R22") (pin "1") (pinfunction "1_1") (pintype "passive"))
    )
    (net (code "86") (name "/GATE15") (class "Default")
      (node (ref "Q16") (pin "1") (pinfunction "G_1") (pintype "passive"))
      (node (ref "R24") (pin "1") (pinfunction "1_1") (pintype "passive"))
    )
    (net (code "87") (name "/GATE16") (class "Default")
      (node (ref "Q20") (pin "1") (pinfunction "G_1") (pintype "passive"))
      (node (ref "R25") (pin "1") (pinfunction "1_1") (pintype "passive"))
    )
    (net (code "88") (name "/GATE17") (class "Default")
      (node (ref "Q19") (pin "1") (pinfunction "G_1") (pintype "passive"))
      (node (ref "R26") (pin "1") (pinfunction "1_1") (pintype "passive"))
    )
    (net (code "89") (name "/GATE18") (class "Default")
      (node (ref "Q18") (pin "1") (pinfunction "G_1") (pintype "passive"))
      (node (ref "R27") (pin "1") (pinfunction "1_1") (pintype "passive"))
    )
    (net (code "90") (name "/GATE19") (class "Default")
      (node (ref "Q17") (pin "1") (pinfunction "G_1") (pintype "passive"))
      (node (ref "R28") (pin "1") (pinfunction "1_1") (pintype "passive"))
    )
    (net (code "91") (name "/GATE20") (class "Default")
      (node (ref "Q21") (pin "1") (pinfunction "G_1") (pintype "passive"))
      (node (ref "R29") (pin "1") (pinfunction "1_1") (pintype "passive"))
    )
    (net (code "92") (name "/GATE21") (class "Default")
      (node (ref "Q22") (pin "1") (pinfunction "G_1") (pintype "passive"))
      (node (ref "R30") (pin "1") (pinfunction "1_1") (pintype "passive"))
    )
    (net (code "93") (name "/GATE22") (class "Default")
      (node (ref "Q23") (pin "1") (pinfunction "G_1") (pintype "passive"))
      (node (ref "R31") (pin "1") (pinfunction "1_1") (pintype "passive"))
    )
    (net (code "94") (name "/GATE23") (class "Default")
      (node (ref "Q24") (pin "1") (pinfunction "G_1") (pintype "passive"))
      (node (ref "R32") (pin "1") (pinfunction "1_1") (pintype "passive"))
    )
    (net (code "95") (name "/GATE24") (class "Default")
      (node (ref "Q28") (pin "1") (pinfunction "G_1") (pintype "passive"))
      (node (ref "R33") (pin "1") (pinfunction "1_1") (pintype "passive"))
    )
    (net (code "96") (name "/GATE25") (class "Default")
      (node (ref "Q27") (pin "1") (pinfunction "G_1") (pintype "passive"))
      (node (ref "R34") (pin "1") (pinfunction "1_1") (pintype "passive"))
    )
    (net (code "97") (name "/GATE26") (class "Default")
      (node (ref "Q26") (pin "1") (pinfunction "G_1") (pintype "passive"))
      (node (ref "R35") (pin "1") (pinfunction "1_1") (pintype "passive"))
    )
    (net (code "98") (name "/GATE27") (class "Default")
      (node (ref "Q25") (pin "1") (pinfunction "G_1") (pintype "passive"))
      (node (ref "R36") (pin "1") (pinfunction "1_1") (pintype "passive"))
    )
    (net (code "99") (name "/GATE28") (class "Default")
      (node (ref "Q29") (pin "1") (pinfunction "G_1") (pintype "passive"))
      (node (ref "R9") (pin "1") (pinfunction "1_1") (pintype "passive"))
    )
    (net (code "100") (name "/GATE29") (class "Default")
      (node (ref "Q30") (pin "1") (pinfunction "G_1") (pintype "passive"))
      (node (ref "R37") (pin "1") (pinfunction "1_1") (pintype "passive"))
    )
    (net (code "101") (name "/GATE30") (class "Default")
      (node (ref "Q31") (pin "1") (pinfunction "G_1") (pintype "passive"))
      (node (ref "R38") (pin "1") (pinfunction "1_1") (pintype "passive"))
    )
    (net (code "102") (name "/GATE31") (class "Default")
      (node (ref "Q32") (pin "1") (pinfunction "G_1") (pintype "passive"))
      (node (ref "R40") (pin "1") (pinfunction "1_1") (pintype "passive"))
    )
    (net (code "103") (name "/IMEAS") (class "Default")
      (node (ref "C20") (pin "2") (pinfunction "2_2") (pintype "passive"))
      (node (ref "R10") (pin "2") (pinfunction "2_2") (pintype "passive"))
      (node (ref "R12") (pin "2") (pinfunction "2_2") (pintype "passive"))
      (node (ref "U3") (pin "6") (pinfunction "PA0_6") (pintype "bidirectional"))
      (node (ref "U7") (pin "6") (pinfunction "VOUT_6") (pintype "output"))
    )
    (net (code "104") (name "/IMEAS_RANGESEL") (class "Default")
      (node (ref "R11") (pin "2") (pinfunction "2_2") (pintype "passive"))
      (node (ref "R12") (pin "1") (pinfunction "1_1") (pintype "passive"))
      (node (ref "U3") (pin "17") (pinfunction "PA9_17") (pintype "bidirectional"))
    )
    (net (code "105") (name "/MOSI") (class "Default")
      (node (ref "U1") (pin "14") (pinfunction "SER_14") (pintype "input"))
      (node (ref "U3") (pin "10") (pinfunction "PA4_10") (pintype "bidirectional"))
    )
    (net (code "106") (name "/NLED1") (class "Default")
      (node (ref "LED1") (pin "2") (pinfunction "K_2") (pintype "passive"))
      (node (ref "U3") (pin "12") (pinfunction "PA6_12") (pintype "bidirectional"))
    )
    (net (code "107") (name "/NLED2") (class "Default")
      (node (ref "LED2") (pin "2") (pinfunction "K_2") (pintype "passive"))
      (node (ref "U3") (pin "13") (pinfunction "PA7_13") (pintype "bidirectional"))
    )
    (net (code "108") (name "/PGND") (class "Default")
      (node (ref "C1") (pin "2") (pinfunction "2_2") (pintype "passive"))
      (node (ref "C5") (pin "2") (pinfunction "2_2") (pintype "passive"))
      (node (ref "C6") (pin "2") (pinfunction "2_2") (pintype "passive"))
      (node (ref "C7") (pin "2") (pinfunction "2_2") (pintype "passive"))
      (node (ref "Q1") (pin "2") (pinfunction "S_2") (pintype "passive"))
      (node (ref "Q10") (pin "2") (pinfunction "S_2") (pintype "passive"))
      (node (ref "Q11") (pin "2") (pinfunction "S_2") (pintype "passive"))
      (node (ref "Q12") (pin "2") (pinfunction "S_2") (pintype "passive"))
      (node (ref "Q13") (pin "2") (pinfunction "S_2") (pintype "passive"))
      (node (ref "Q14") (pin "2") (pinfunction "S_2") (pintype "passive"))
      (node (ref "Q15") (pin "2") (pinfunction "S_2") (pintype "passive"))
      (node (ref "Q16") (pin "2") (pinfunction "S_2") (pintype "passive"))
      (node (ref "Q17") (pin "2") (pinfunction "S_2") (pintype "passive"))
      (node (ref "Q18") (pin "2") (pinfunction "S_2") (pintype "passive"))
      (node (ref "Q19") (pin "2") (pinfunction "S_2") (pintype "passive"))
      (node (ref "Q2") (pin "2") (pinfunction "S_2") (pintype "passive"))
      (node (ref "Q20") (pin "2") (pinfunction "S_2") (pintype "passive"))
      (node (ref "Q21") (pin "2") (pinfunction "S_2") (pintype "passive"))
      (node (ref "Q22") (pin "2") (pinfunction "S_2") (pintype "passive"))
      (node (ref "Q23") (pin "2") (pinfunction "S_2") (pintype "passive"))
      (node (ref "Q24") (pin "2") (pinfunction "S_2") (pintype "passive"))
      (node (ref "Q25") (pin "2") (pinfunction "S_2") (pintype "passive"))
      (node (ref "Q26") (pin "2") (pinfunction "S_2") (pintype "passive"))
      (node (ref "Q27") (pin "2") (pinfunction "S_2") (pintype "passive"))
      (node (ref "Q28") (pin "2") (pinfunction "S_2") (pintype "passive"))
      (node (ref "Q29") (pin "2") (pinfunction "S_2") (pintype "passive"))
      (node (ref "Q3") (pin "2") (pinfunction "S_2") (pintype "passive"))
      (node (ref "Q30") (pin "2") (pinfunction "S_2") (pintype "passive"))
      (node (ref "Q31") (pin "2") (pinfunction "S_2") (pintype "passive"))
      (node (ref "Q32") (pin "2") (pinfunction "S_2") (pintype "passive"))
      (node (ref "Q4") (pin "2") (pinfunction "S_2") (pintype "passive"))
      (node (ref "Q5") (pin "2") (pinfunction "S_2") (pintype "passive"))
      (node (ref "Q6") (pin "2") (pinfunction "S_2") (pintype "passive"))
      (node (ref "Q7") (pin "2") (pinfunction "S_2") (pintype "passive"))
      (node (ref "Q8") (pin "2") (pinfunction "S_2") (pintype "passive"))
      (node (ref "Q9") (pin "2") (pinfunction "S_2") (pintype "passive"))
      (node (ref "R39") (pin "1") (pinfunction "1_1") (pintype "passive"))
      (node (ref "R41") (pin "1") (pinfunction "1_1") (pintype "passive"))
    )
    (net (code "109") (name "/RESET") (class "Default")
      (node (ref "C4") (pin "1") (pinfunction "1_1") (pintype "passive"))
      (node (ref "J5") (pin "1") (pinfunction "1_1") (pintype "passive"))
      (node (ref "R21") (pin "1") (pinfunction "1_1") (pintype "passive"))
      (node (ref "U3") (pin "4") (pinfunction "NRST_4") (pintype "bidirectional"))
    )
    (net (code "110") (name "/RS485_DN") (class "Default")
      (node (ref "J1") (pin "4") (pintype "passive"))
      (node (ref "U2") (pin "6") (pinfunction "DO/RI_6") (pintype "bidirectional"))
    )
    (net (code "111") (name "/RS485_DP") (class "Default")
      (node (ref "J1") (pin "3") (pintype "passive"))
      (node (ref "U2") (pin "7") (pinfunction "~{DO}/~{RI}_7") (pintype "bidirectional"))
    )
    (net (code "112") (name "/RX") (class "Default")
      (node (ref "U2") (pin "1") (pinfunction "RO_1") (pintype "output"))
      (node (ref "U3") (pin "9") (pinfunction "PA3_9") (pintype "bidirectional"))
    )
    (net (code "113") (name "/SCLK") (class "Default")
      (node (ref "U1") (pin "11") (pinfunction "SRCLK_11") (pintype "input"))
      (node (ref "U3") (pin "11") (pinfunction "PA5_11") (pintype "bidirectional"))
      (node (ref "U4") (pin "11") (pinfunction "SRCLK_11") (pintype "input"))
      (node (ref "U5") (pin "11") (pinfunction "SRCLK_11") (pintype "input"))
      (node (ref "U6") (pin "11") (pinfunction "SRCLK_11") (pintype "input"))
    )
    (net (code "114") (name "/STROBE") (class "Default")
      (node (ref "U1") (pin "12") (pinfunction "RCLK_12") (pintype "input"))
      (node (ref "U3") (pin "18") (pinfunction "PA10_18") (pintype "bidirectional"))
      (node (ref "U4") (pin "12") (pinfunction "RCLK_12") (pintype "input"))
      (node (ref "U5") (pin "12") (pinfunction "RCLK_12") (pintype "input"))
      (node (ref "U6") (pin "12") (pinfunction "RCLK_12") (pintype "input"))
    )
    (net (code "115") (name "/SWCLK") (class "Default")
      (node (ref "J5") (pin "2") (pinfunction "2_2") (pintype "passive"))
      (node (ref "U3") (pin "20") (pinfunction "PA14(SWCLK)_20") (pintype "bidirectional"))
    )
    (net (code "116") (name "/SWDIO") (class "Default")
      (node (ref "J5") (pin "3") (pinfunction "3_3") (pintype "passive"))
      (node (ref "U3") (pin "19") (pinfunction "PA13(SWDIO)_19") (pintype "bidirectional"))
    )
    (net (code "117") (name "/TX") (class "Default")
      (node (ref "U2") (pin "4") (pinfunction "DI_4") (pintype "input"))
      (node (ref "U3") (pin "8") (pinfunction "PA2_8") (pintype "bidirectional"))
    )
    (net (code "118") (name "/TXEN") (class "Default")
      (node (ref "U2") (pin "2") (pinfunction "~{RE}_2") (pintype "input"))
      (node (ref "U2") (pin "3") (pinfunction "DE_3") (pintype "input"))
      (node (ref "U3") (pin "7") (pinfunction "PA1_7") (pintype "bidirectional"))
    )
    (net (code "119") (name "/XT1") (class "Default")
      (node (ref "C2") (pin "2") (pinfunction "2_2") (pintype "passive"))
      (node (ref "U3") (pin "2") (pinfunction "PF0-OSC_IN(PF0)_2") (pintype "bidirectional"))
      (node (ref "Y1") (pin "1") (pinfunction "X1_1") (pintype "passive"))
    )
    (net (code "120") (name "/XT2") (class "Default")
      (node (ref "C3") (pin "1") (pinfunction "1_1") (pintype "passive"))
      (node (ref "U3") (pin "3") (pinfunction "PF1-OSC_OUT(PF1)_3") (pintype "bidirectional"))
      (node (ref "Y1") (pin "3") (pinfunction "X2_3") (pintype "passive"))
    )
    (net (code "121") (name "AVCC") (class "Default")
      (node (ref "C16") (pin "1") (pinfunction "1_1") (pintype "passive"))
      (node (ref "C17") (pin "1") (pinfunction "1_1") (pintype "passive"))
      (node (ref "R44") (pin "2") (pinfunction "2_2") (pintype "passive"))
      (node (ref "U7") (pin "7") (pinfunction "VDD_7") (pintype "power_in"))
    )
    (net (code "122") (name "AVCC2") (class "Default")
      (node (ref "C18") (pin "1") (pinfunction "1_1") (pintype "passive"))
      (node (ref "C19") (pin "1") (pinfunction "1_1") (pintype "passive"))
      (node (ref "R43") (pin "2") (pinfunction "2_2") (pintype "passive"))
      (node (ref "U3") (pin "5") (pinfunction "VDDA_5") (pintype "power_in"))
    )
    (net (code "123") (name "GND") (class "Default")
      (node (ref "C10") (pin "2") (pinfunction "2_2") (pintype "passive"))
      (node (ref "C11") (pin "2") (pinfunction "2_2") (pintype "passive"))
      (node (ref "C12") (pin "2") (pinfunction "2_2") (pintype "passive"))
      (node (ref "C13") (pin "2") (pinfunction "2_2") (pintype "passive"))
      (node (ref "C14") (pin "2") (pinfunction "2_2") (pintype "passive"))
      (node (ref "C15") (pin "2") (pinfunction "2_2") (pintype "passive"))
      (node (ref "C16") (pin "2") (pinfunction "2_2") (pintype "passive"))
      (node (ref "C17") (pin "2") (pinfunction "2_2") (pintype "passive"))
      (node (ref "C18") (pin "2") (pinfunction "2_2") (pintype "passive"))
      (node (ref "C19") (pin "2") (pinfunction "2_2") (pintype "passive"))
      (node (ref "C2") (pin "1") (pinfunction "1_1") (pintype "passive"))
      (node (ref "C3") (pin "2") (pinfunction "2_2") (pintype "passive"))
      (node (ref "C4") (pin "2") (pinfunction "2_2") (pintype "passive"))
      (node (ref "C8") (pin "2") (pinfunction "2_2") (pintype "passive"))
      (node (ref "C9") (pin "2") (pinfunction "2_2") (pintype "passive"))
      (node (ref "IC1") (pin "1") (pinfunction "GND_1") (pintype "passive"))
      (node (ref "J1") (pin "2") (pintype "passive"))
      (node (ref "J5") (pin "4") (pinfunction "4_4") (pintype "passive"))
      (node (ref "J9") (pin "1") (pinfunction "1_1") (pintype "passive"))
      (node (ref "R20") (pin "1") (pinfunction "1_1") (pintype "passive"))
      (node (ref "R41") (pin "2") (pinfunction "2_2") (pintype "passive"))
      (node (ref "R42") (pin "1") (pinfunction "1_1") (pintype "passive"))
      (node (ref "U1") (pin "13") (pinfunction "~{OE}_13") (pintype "input"))
      (node (ref "U1") (pin "8") (pinfunction "GND_8") (pintype "power_in"))
      (node (ref "U2") (pin "5") (pinfunction "GND_5") (pintype "power_in"))
      (node (ref "U3") (pin "15") (pinfunction "VSS_15") (pintype "power_in"))
      (node (ref "U4") (pin "13") (pinfunction "~{OE}_13") (pintype "input"))
      (node (ref "U4") (pin "8") (pinfunction "GND_8") (pintype "power_in"))
      (node (ref "U5") (pin "13") (pinfunction "~{OE}_13") (pintype "input"))
      (node (ref "U5") (pin "8") (pinfunction "GND_8") (pintype "power_in"))
      (node (ref "U6") (pin "13") (pinfunction "~{OE}_13") (pintype "input"))
      (node (ref "U6") (pin "8") (pinfunction "GND_8") (pintype "power_in"))
      (node (ref "U7") (pin "4") (pinfunction "VSS_4") (pintype "power_in"))
      (node (ref "Y1") (pin "2") (pinfunction "GND_2") (pintype "power_in"))
      (node (ref "Y1") (pin "4") (pinfunction "GND_4") (pintype "power_in"))
    )
    (net (code "124") (name "Net-(LED1-A)") (class "Default")
      (node (ref "LED1") (pin "1") (pinfunction "A_1") (pintype "passive"))
      (node (ref "R1") (pin "1") (pinfunction "1_1") (pintype "passive"))
    )
    (net (code "125") (name "Net-(LED2-A)") (class "Default")
      (node (ref "LED2") (pin "1") (pinfunction "A_1") (pintype "passive"))
      (node (ref "R2") (pin "1") (pinfunction "1_1") (pintype "passive"))
    )
    (net (code "126") (name "Net-(Q15-G)") (class "Default")
      (node (ref "Q15") (pin "1") (pinfunction "G_1") (pintype "passive"))
      (node (ref "R23") (pin "1") (pinfunction "1_1") (pintype "passive"))
    )
    (net (code "127") (name "Net-(U7-VIN+)") (class "Default")
      (node (ref "R39") (pin "2") (pinfunction "2_2") (pintype "passive"))
      (node (ref "U7") (pin "3") (pinfunction "VIN+_3") (pintype "input"))
    )
    (net (code "128") (name "Net-(U7-VIN-)") (class "Default")
      (node (ref "C20") (pin "1") (pinfunction "1_1") (pintype "passive"))
      (node (ref "R10") (pin "1") (pinfunction "1_1") (pintype "passive"))
      (node (ref "R11") (pin "1") (pinfunction "1_1") (pintype "passive"))
      (node (ref "R42") (pin "2") (pinfunction "2_2") (pintype "passive"))
      (node (ref "U7") (pin "2") (pinfunction "VIN-_2") (pintype "input"))
    )
    (net (code "129") (name "VCC") (class "Default")
      (node (ref "C10") (pin "1") (pinfunction "1_1") (pintype "passive"))
      (node (ref "C11") (pin "1") (pinfunction "1_1") (pintype "passive"))
      (node (ref "C12") (pin "1") (pinfunction "1_1") (pintype "passive"))
      (node (ref "C13") (pin "1") (pinfunction "1_1") (pintype "passive"))
      (node (ref "C14") (pin "1") (pinfunction "1_1") (pintype "passive"))
      (node (ref "C15") (pin "1") (pinfunction "1_1") (pintype "passive"))
      (node (ref "IC1") (pin "2") (pinfunction "OUT_2") (pintype "passive"))
      (node (ref "IC1") (pin "4") (pinfunction "OUT_4") (pintype "passive"))
      (node (ref "J4") (pin "1") (pinfunction "1_1") (pintype "passive"))
      (node (ref "R1") (pin "2") (pinfunction "2_2") (pintype "passive"))
      (node (ref "R2") (pin "2") (pinfunction "2_2") (pintype "passive"))
      (node (ref "R21") (pin "2") (pinfunction "2_2") (pintype "passive"))
      (node (ref "R43") (pin "1") (pinfunction "1_1") (pintype "passive"))
      (node (ref "R44") (pin "1") (pinfunction "1_1") (pintype "passive"))
      (node (ref "U1") (pin "16") (pinfunction "VCC_16") (pintype "power_in"))
      (node (ref "U2") (pin "8") (pinfunction "VCC_8") (pintype "power_in"))
      (node (ref "U3") (pin "16") (pinfunction "VDD_16") (pintype "power_in"))
      (node (ref "U4") (pin "16") (pinfunction "VCC_16") (pintype "power_in"))
      (node (ref "U5") (pin "16") (pinfunction "VCC_16") (pintype "power_in"))
      (node (ref "U6") (pin "16") (pinfunction "VCC_16") (pintype "power_in"))
    )
    (net (code "130") (name "unconnected-(J2-Pad3)") (class "Default")
      (node (ref "J2") (pin "3") (pinfunction "3_3") (pintype "passive"))
    )
    (net (code "131") (name "unconnected-(J3-Pad3)") (class "Default")
      (node (ref "J3") (pin "3") (pinfunction "3_3") (pintype "passive"))
    )
    (net (code "132") (name "unconnected-(J6-Pad3)") (class "Default")
      (node (ref "J6") (pin "3") (pinfunction "3_3") (pintype "passive"))
    )
    (net (code "133") (name "unconnected-(J7-Pad3)") (class "Default")
      (node (ref "J7") (pin "3") (pinfunction "3_3") (pintype "passive"))
    )
    (net (code "134") (name "unconnected-(U6-QH'-Pad9)") (class "Default")
      (node (ref "U6") (pin "9") (pinfunction "QH'_9") (pintype "output+no_connect"))
    )
    (net (code "135") (name "unconnected-(U7-NC-Pad1)") (class "Default")
      (node (ref "U7") (pin "1") (pinfunction "NC_1") (pintype "passive+no_connect"))
    )
    (net (code "136") (name "unconnected-(U7-NC-Pad5)") (class "Default")
      (node (ref "U7") (pin "5") (pinfunction "NC_5") (pintype "passive+no_connect"))
    )
    (net (code "137") (name "unconnected-(U7-NC-Pad8)") (class "Default")
      (node (ref "U7") (pin "8") (pinfunction "NC_8") (pintype "passive"))
    )
  )
)
